# WeldingRectifier.net
KiCad netlist of a schematic drawn in EAGLE
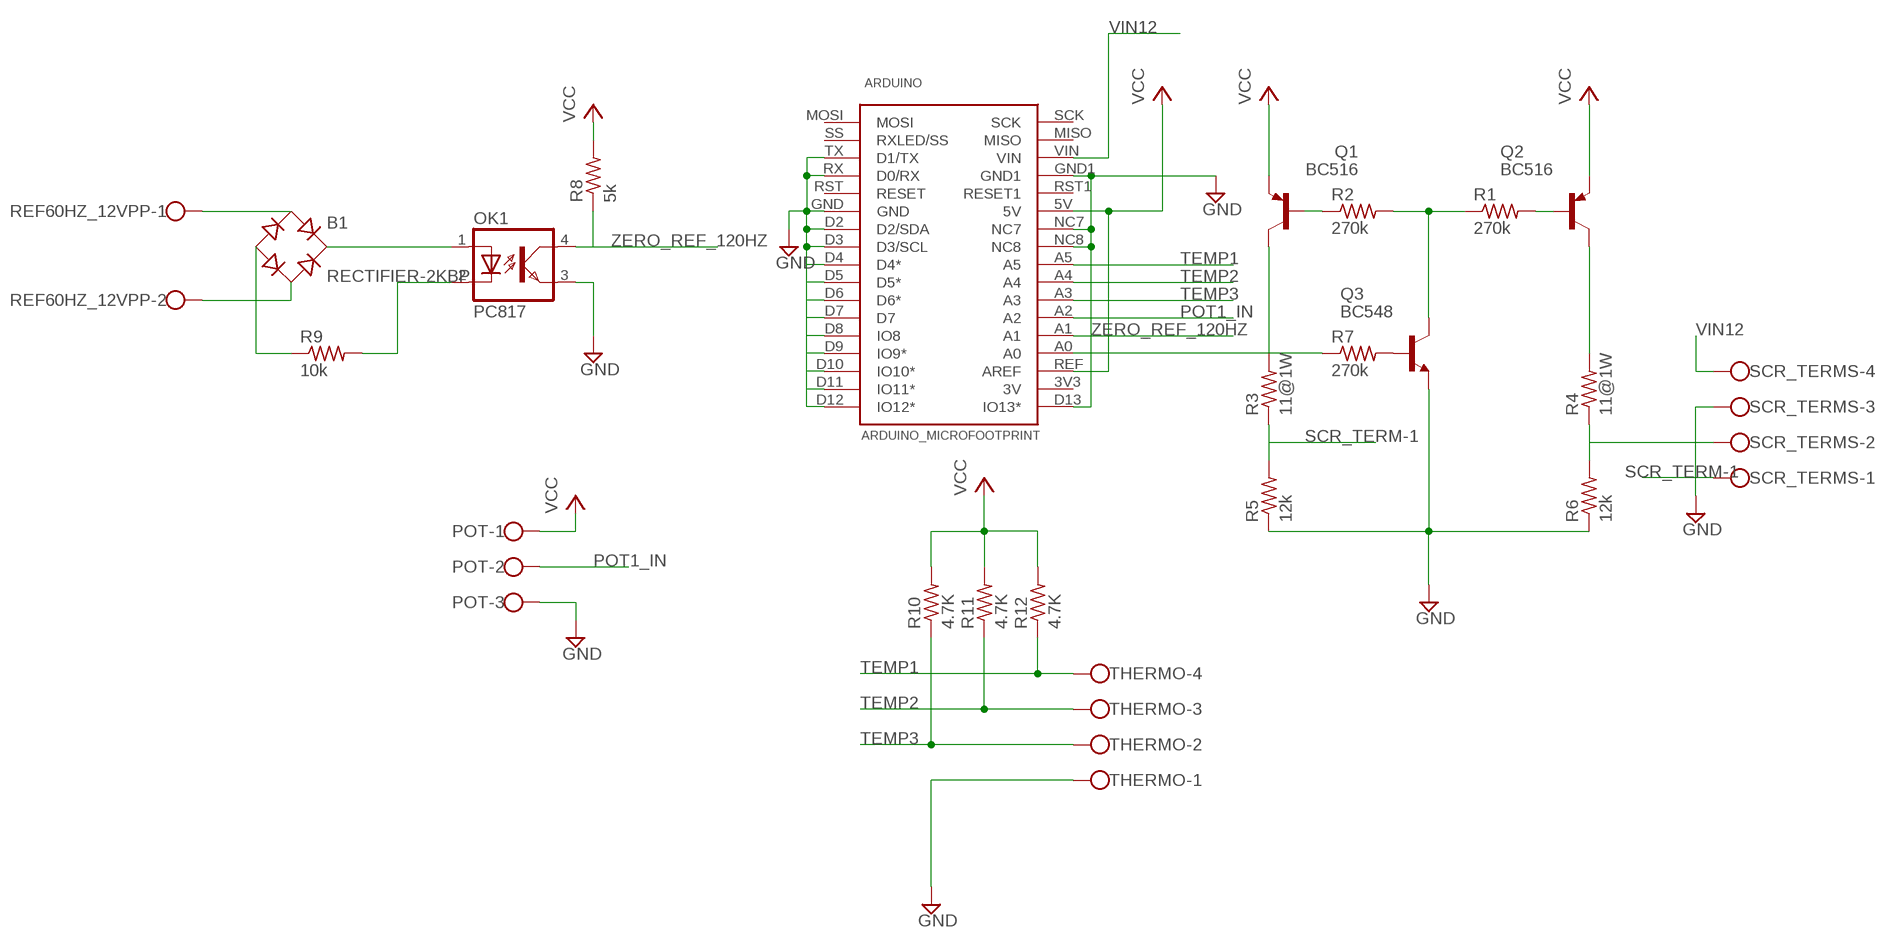
[diagram p0: schematic, sheet 1]

(export (version "E")
  (design (tool "Eeschema 10.0.6"))
  (components
    (comp (ref "ARDUINO")
      (value "ARDUINO_MICROFOOTPRINT")
      (footprint "eagle-import:ARDUINO-MICRO")
      (libsource (lib "eagle-import") (part "ARDUINO_MICROFOOTPRINT"))
    )
    (comp (ref "B1")
      (value "RECTIFIER-2KBP")
      (footprint "eagle-import:2KBP")
      (libsource (lib "eagle-import") (part "RECTIFIER-2KBP"))
    )
    (comp (ref "OK1")
      (value "PC817")
      (footprint "eagle-import:DIL04")
      (fields (field (name "MPN") "PC817X4J000F"))
      (libsource (lib "eagle-import") (part "PC817"))
    )
    (comp (ref "POT")
      (value "W237-103")
      (footprint "eagle-import:W237-103")
      (fields (field (name "MPN") "237-103"))
      (libsource (lib "eagle-import") (part "W237-103"))
    )
    (comp (ref "Q1")
      (value "BC516")
      (footprint "eagle-import:TO92-EBC")
      (libsource (lib "eagle-import") (part "BC516"))
    )
    (comp (ref "Q2")
      (value "BC516")
      (footprint "eagle-import:TO92-EBC")
      (libsource (lib "eagle-import") (part "BC516"))
    )
    (comp (ref "Q3")
      (value "BC548")
      (footprint "eagle-import:TO92-EBC")
      (libsource (lib "eagle-import") (part "BC548"))
    )
    (comp (ref "R1")
      (value "270k")
      (footprint "eagle-import:0204_7")
      (libsource (lib "eagle-import") (part "R-US_0204/7"))
    )
    (comp (ref "R2")
      (value "270k")
      (footprint "eagle-import:0204_7")
      (libsource (lib "eagle-import") (part "R-US_0204/7"))
    )
    (comp (ref "R3")
      (value "11@1W")
      (footprint "eagle-import:0204_7")
      (libsource (lib "eagle-import") (part "R-US_0204/7"))
    )
    (comp (ref "R4")
      (value "11@1W")
      (footprint "eagle-import:0204_7")
      (libsource (lib "eagle-import") (part "R-US_0204/7"))
    )
    (comp (ref "R5")
      (value "12k")
      (footprint "eagle-import:0204_7")
      (libsource (lib "eagle-import") (part "R-US_0204/7"))
    )
    (comp (ref "R6")
      (value "12k")
      (footprint "eagle-import:0204_7")
      (libsource (lib "eagle-import") (part "R-US_0204/7"))
    )
    (comp (ref "R7")
      (value "270k")
      (footprint "eagle-import:0204_7")
      (libsource (lib "eagle-import") (part "R-US_0204/7"))
    )
    (comp (ref "R8")
      (value "5k")
      (footprint "eagle-import:0204_7")
      (libsource (lib "eagle-import") (part "R-US_0204/7"))
    )
    (comp (ref "R9")
      (value "10k")
      (footprint "eagle-import:0204_7")
      (libsource (lib "eagle-import") (part "R-US_0204/7"))
    )
    (comp (ref "R10")
      (value "4.7K")
      (footprint "eagle-import:0204_7")
      (libsource (lib "eagle-import") (part "R-US_0204/7"))
    )
    (comp (ref "R11")
      (value "4.7K")
      (footprint "eagle-import:0204_7")
      (libsource (lib "eagle-import") (part "R-US_0204/7"))
    )
    (comp (ref "R12")
      (value "4.7K")
      (footprint "eagle-import:0204_7")
      (libsource (lib "eagle-import") (part "R-US_0204/7"))
    )
    (comp (ref "REF60HZ_12VPP")
      (value "W237-102")
      (footprint "eagle-import:W237-102")
      (fields (field (name "MPN") "237-102"))
      (libsource (lib "eagle-import") (part "W237-102"))
    )
    (comp (ref "SCR_TERMS")
      (value "W237-4")
      (footprint "eagle-import:W237-4")
      (libsource (lib "eagle-import") (part "W237-4"))
    )
    (comp (ref "THERMO")
      (value "W237-4")
      (footprint "eagle-import:W237-4")
      (libsource (lib "eagle-import") (part "W237-4"))
    )
  )
  (nets
    (net (code "1") (name "/POT1_IN") (class "Default")
      (node (ref "ARDUINO") (pin "A2") (pinfunction "A2_A2") (pintype "bidirectional"))
      (node (ref "POT") (pin "2") (pinfunction "KL_2") (pintype "passive"))
    )
    (net (code "2") (name "/SCR_TERM-1") (class "Default")
      (node (ref "R3") (pin "1") (pinfunction "1_1") (pintype "passive"))
      (node (ref "R5") (pin "2") (pinfunction "2_2") (pintype "passive"))
      (node (ref "SCR_TERMS") (pin "1") (pinfunction "KL_1") (pintype "passive"))
    )
    (net (code "3") (name "/TEMP1") (class "Default")
      (node (ref "ARDUINO") (pin "A5") (pinfunction "A5_A5") (pintype "bidirectional"))
      (node (ref "R12") (pin "1") (pinfunction "1_1") (pintype "passive"))
      (node (ref "THERMO") (pin "4") (pinfunction "KL_4") (pintype "passive"))
    )
    (net (code "4") (name "/TEMP2") (class "Default")
      (node (ref "ARDUINO") (pin "A4") (pinfunction "A4_A4") (pintype "bidirectional"))
      (node (ref "R11") (pin "1") (pinfunction "1_1") (pintype "passive"))
      (node (ref "THERMO") (pin "3") (pinfunction "KL_3") (pintype "passive"))
    )
    (net (code "5") (name "/TEMP3") (class "Default")
      (node (ref "ARDUINO") (pin "A3") (pinfunction "A3_A3") (pintype "bidirectional"))
      (node (ref "R10") (pin "1") (pinfunction "1_1") (pintype "passive"))
      (node (ref "THERMO") (pin "2") (pinfunction "KL_2") (pintype "passive"))
    )
    (net (code "6") (name "/VIN12") (class "Default")
      (node (ref "ARDUINO") (pin "VIN") (pinfunction "VIN_VIN") (pintype "bidirectional"))
      (node (ref "SCR_TERMS") (pin "4") (pinfunction "KL_4") (pintype "passive"))
    )
    (net (code "7") (name "/ZERO_REF_120HZ") (class "Default")
      (node (ref "ARDUINO") (pin "A1") (pinfunction "A1_A1") (pintype "bidirectional"))
      (node (ref "OK1") (pin "4") (pinfunction "COL_4") (pintype "passive"))
      (node (ref "R8") (pin "1") (pinfunction "1_1") (pintype "passive"))
    )
    (net (code "8") (name "GND") (class "Default")
      (node (ref "ARDUINO") (pin "D10") (pinfunction "IO10*_D10") (pintype "bidirectional"))
      (node (ref "ARDUINO") (pin "D11") (pinfunction "IO11*_D11") (pintype "bidirectional"))
      (node (ref "ARDUINO") (pin "D12") (pinfunction "IO12*_D12") (pintype "bidirectional"))
      (node (ref "ARDUINO") (pin "D13") (pinfunction "IO13*_D13") (pintype "bidirectional"))
      (node (ref "ARDUINO") (pin "D2") (pinfunction "D2/SDA_D2") (pintype "bidirectional"))
      (node (ref "ARDUINO") (pin "D3") (pinfunction "D3/SCL_D3") (pintype "bidirectional"))
      (node (ref "ARDUINO") (pin "D4") (pinfunction "D4*_D4") (pintype "bidirectional"))
      (node (ref "ARDUINO") (pin "D5") (pinfunction "D5*_D5") (pintype "bidirectional"))
      (node (ref "ARDUINO") (pin "D6") (pinfunction "D6*_D6") (pintype "bidirectional"))
      (node (ref "ARDUINO") (pin "D7") (pinfunction "D7_D7") (pintype "bidirectional"))
      (node (ref "ARDUINO") (pin "D8") (pinfunction "IO8_D8") (pintype "bidirectional"))
      (node (ref "ARDUINO") (pin "D9") (pinfunction "IO9*_D9") (pintype "bidirectional"))
      (node (ref "ARDUINO") (pin "GND") (pinfunction "GND_GND") (pintype "bidirectional"))
      (node (ref "ARDUINO") (pin "GND1") (pinfunction "GND1_GND1") (pintype "bidirectional"))
      (node (ref "ARDUINO") (pin "NC7") (pinfunction "NC7_NC7") (pintype "bidirectional"))
      (node (ref "ARDUINO") (pin "NC8") (pinfunction "NC8_NC8") (pintype "bidirectional"))
      (node (ref "ARDUINO") (pin "RX") (pinfunction "D0/RX_RX") (pintype "bidirectional"))
      (node (ref "ARDUINO") (pin "TX") (pinfunction "D1/TX_TX") (pintype "bidirectional"))
      (node (ref "OK1") (pin "3") (pinfunction "EMIT_3") (pintype "passive"))
      (node (ref "POT") (pin "3") (pinfunction "KL_3") (pintype "passive"))
      (node (ref "Q3") (pin "E") (pinfunction "E_E") (pintype "passive"))
      (node (ref "R5") (pin "1") (pinfunction "1_1") (pintype "passive"))
      (node (ref "R6") (pin "1") (pinfunction "1_1") (pintype "passive"))
      (node (ref "SCR_TERMS") (pin "3") (pinfunction "KL_3") (pintype "passive"))
      (node (ref "THERMO") (pin "1") (pinfunction "KL_1") (pintype "passive"))
    )
    (net (code "9") (name "Net-(ARDUINO-PadA0)") (class "Default")
      (node (ref "ARDUINO") (pin "A0") (pinfunction "A0_A0") (pintype "bidirectional"))
      (node (ref "R7") (pin "1") (pinfunction "1_1") (pintype "passive"))
    )
    (net (code "10") (name "Net-(B1-Pad-)") (class "Default")
      (node (ref "B1") (pin "-") (pinfunction "-_-") (pintype "passive"))
      (node (ref "R9") (pin "1") (pinfunction "1_1") (pintype "passive"))
    )
    (net (code "11") (name "Net-(OK1-A)") (class "Default")
      (node (ref "B1") (pin "+") (pinfunction "+_+") (pintype "passive"))
      (node (ref "OK1") (pin "1") (pinfunction "A_1") (pintype "passive"))
    )
    (net (code "12") (name "Net-(OK1-C)") (class "Default")
      (node (ref "OK1") (pin "2") (pinfunction "C_2") (pintype "passive"))
      (node (ref "R9") (pin "2") (pinfunction "2_2") (pintype "passive"))
    )
    (net (code "13") (name "Net-(Q1-PadB)") (class "Default")
      (node (ref "Q1") (pin "B") (pinfunction "B_B") (pintype "passive"))
      (node (ref "R2") (pin "1") (pinfunction "1_1") (pintype "passive"))
    )
    (net (code "14") (name "Net-(Q1-PadC)") (class "Default")
      (node (ref "Q1") (pin "C") (pinfunction "C_C") (pintype "passive"))
      (node (ref "R3") (pin "2") (pinfunction "2_2") (pintype "passive"))
    )
    (net (code "15") (name "Net-(Q2-PadB)") (class "Default")
      (node (ref "Q2") (pin "B") (pinfunction "B_B") (pintype "passive"))
      (node (ref "R1") (pin "2") (pinfunction "2_2") (pintype "passive"))
    )
    (net (code "16") (name "Net-(Q2-PadC)") (class "Default")
      (node (ref "Q2") (pin "C") (pinfunction "C_C") (pintype "passive"))
      (node (ref "R4") (pin "2") (pinfunction "2_2") (pintype "passive"))
    )
    (net (code "17") (name "Net-(Q3-PadB)") (class "Default")
      (node (ref "Q3") (pin "B") (pinfunction "B_B") (pintype "passive"))
      (node (ref "R7") (pin "2") (pinfunction "2_2") (pintype "passive"))
    )
    (net (code "18") (name "Net-(Q3-PadC)") (class "Default")
      (node (ref "Q3") (pin "C") (pinfunction "C_C") (pintype "passive"))
      (node (ref "R1") (pin "1") (pinfunction "1_1") (pintype "passive"))
      (node (ref "R2") (pin "2") (pinfunction "2_2") (pintype "passive"))
    )
    (net (code "19") (name "Net-(REF60HZ_12VPPA-KL)") (class "Default")
      (node (ref "B1") (pin "AC1") (pinfunction "AC1_AC1") (pintype "passive"))
      (node (ref "REF60HZ_12VPP") (pin "1") (pinfunction "KL_1") (pintype "passive"))
    )
    (net (code "20") (name "Net-(REF60HZ_12VPPB-KL)") (class "Default")
      (node (ref "B1") (pin "AC2") (pinfunction "AC2_AC2") (pintype "passive"))
      (node (ref "REF60HZ_12VPP") (pin "2") (pinfunction "KL_2") (pintype "passive"))
    )
    (net (code "21") (name "Net-(SCR_TERMSB-KL)") (class "Default")
      (node (ref "R4") (pin "1") (pinfunction "1_1") (pintype "passive"))
      (node (ref "R6") (pin "2") (pinfunction "2_2") (pintype "passive"))
      (node (ref "SCR_TERMS") (pin "2") (pinfunction "KL_2") (pintype "passive"))
    )
    (net (code "22") (name "VCC") (class "Default")
      (node (ref "ARDUINO") (pin "5V") (pinfunction "5V_5V") (pintype "bidirectional"))
      (node (ref "ARDUINO") (pin "REF") (pinfunction "AREF_REF") (pintype "bidirectional"))
      (node (ref "POT") (pin "1") (pinfunction "KL_1") (pintype "passive"))
      (node (ref "Q1") (pin "E") (pinfunction "E_E") (pintype "passive"))
      (node (ref "Q2") (pin "E") (pinfunction "E_E") (pintype "passive"))
      (node (ref "R10") (pin "2") (pinfunction "2_2") (pintype "passive"))
      (node (ref "R11") (pin "2") (pinfunction "2_2") (pintype "passive"))
      (node (ref "R12") (pin "2") (pinfunction "2_2") (pintype "passive"))
      (node (ref "R8") (pin "2") (pinfunction "2_2") (pintype "passive"))
    )
    (net (code "23") (name "unconnected-(ARDUINO-3V-Pad3V3)") (class "Default")
      (node (ref "ARDUINO") (pin "3V3") (pinfunction "3V_3V3") (pintype "bidirectional"))
    )
    (net (code "24") (name "unconnected-(ARDUINO-PadMISO)") (class "Default")
      (node (ref "ARDUINO") (pin "MISO") (pinfunction "MISO_MISO") (pintype "bidirectional"))
    )
    (net (code "25") (name "unconnected-(ARDUINO-PadMOSI)") (class "Default")
      (node (ref "ARDUINO") (pin "MOSI") (pinfunction "MOSI_MOSI") (pintype "bidirectional"))
    )
    (net (code "26") (name "unconnected-(ARDUINO-PadSCK)") (class "Default")
      (node (ref "ARDUINO") (pin "SCK") (pinfunction "SCK_SCK") (pintype "bidirectional"))
    )
    (net (code "27") (name "unconnected-(ARDUINO-RESET-PadRST)") (class "Default")
      (node (ref "ARDUINO") (pin "RST") (pinfunction "RESET_RST") (pintype "bidirectional"))
    )
    (net (code "28") (name "unconnected-(ARDUINO-RESET1-PadRST1)") (class "Default")
      (node (ref "ARDUINO") (pin "RST1") (pinfunction "RESET1_RST1") (pintype "bidirectional"))
    )
    (net (code "29") (name "unconnected-(ARDUINO-RXLED{slash}SS-PadSS)") (class "Default")
      (node (ref "ARDUINO") (pin "SS") (pinfunction "RXLED/SS_SS") (pintype "bidirectional"))
    )
  )
)
